# ST_LINK_V2-1.net
KiCad netlist of a schematic drawn in Altium Designer
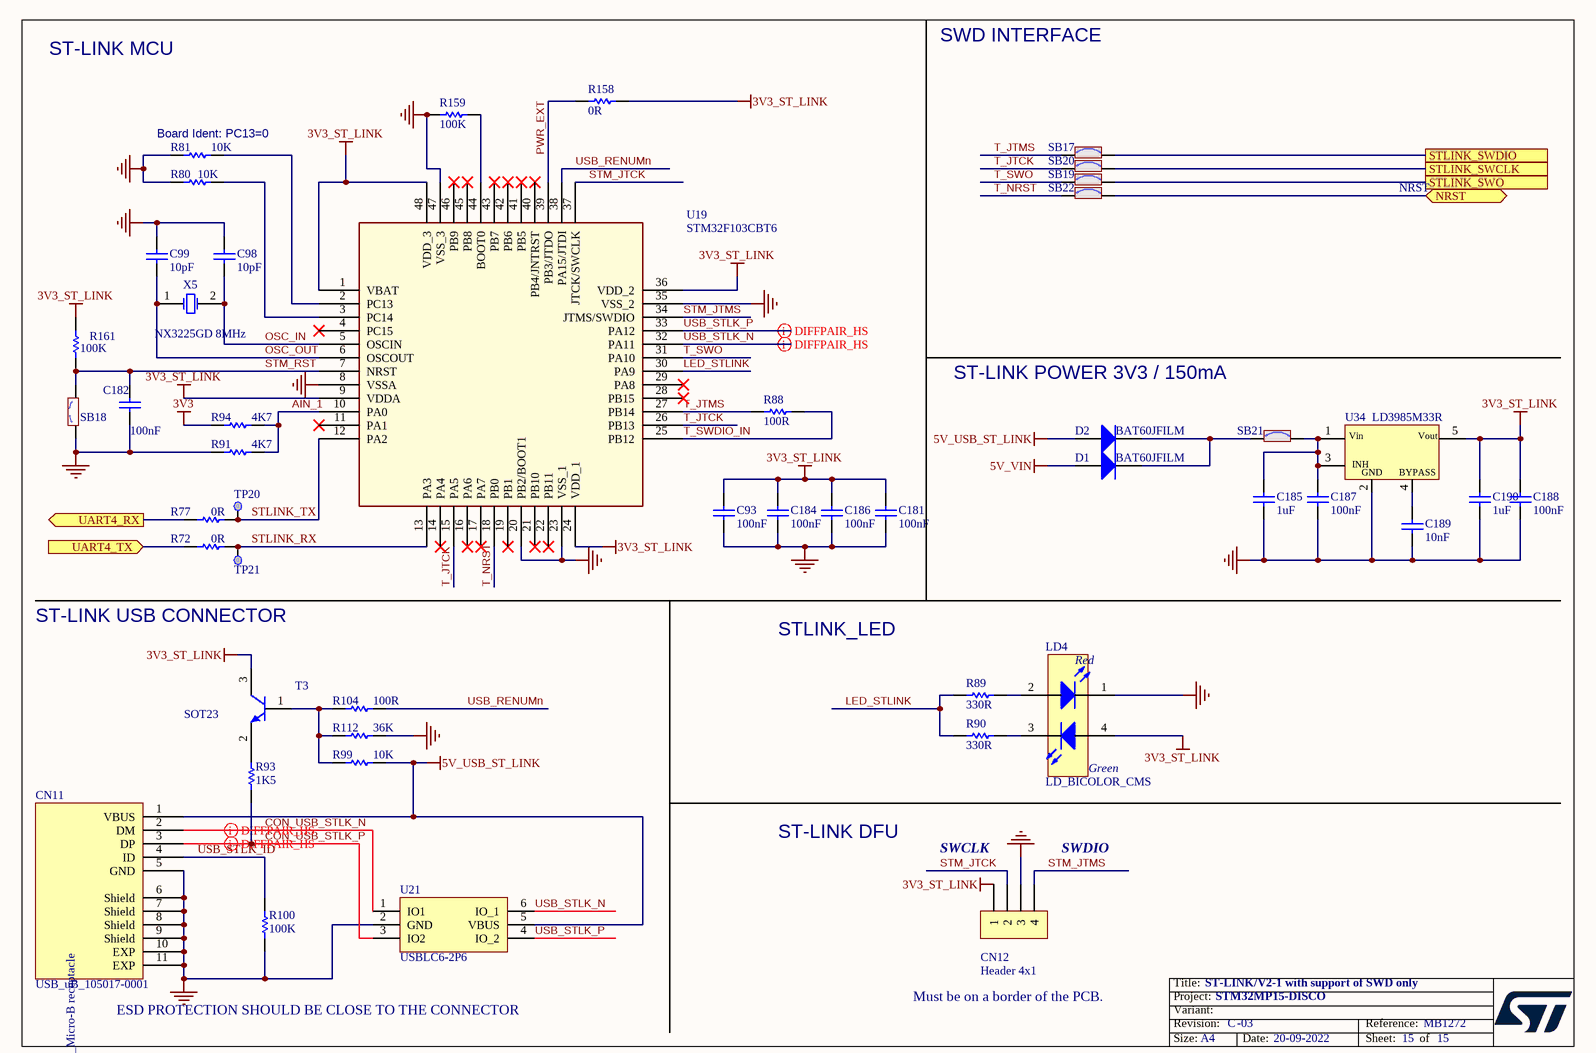
[diagram p0: ST_LINK_V2-1.SCHDOC]

(export (version "E")
  (design (tool "Eeschema 10.0.6"))
  (components
    (comp (ref "C93")
      (value "100nF")
      (footprint "C0402")
      (description "Capacitor,100nF,16V,X7R,10%,0402")
      (fields
        (field (name "INTERNAL_PART_NUMBER") "MCD-00006")
        (field (name "MANUFACTURER_PART_NUMBER") "CC0402KRX7R7BB104")
        (field (name "PROVIDED_BY") "SUBCO")
      )
      (libsource (lib "MCD_PARTS_database") (part "Capacitor"))
    )
    (comp (ref "C98")
      (value "10pF")
      (footprint "C0402")
      (description "Capacitor,10pF,50V,NPO,5%,0402")
      (fields
        (field (name "INTERNAL_PART_NUMBER") "MCD-00015")
        (field (name "MANUFACTURER_PART_NUMBER") "CC0402JRNPO9BN100")
        (field (name "PROVIDED_BY") "SUBCO")
      )
      (libsource (lib "MCD_PARTS_database") (part "Capacitor"))
    )
    (comp (ref "C99")
      (value "10pF")
      (footprint "C0402")
      (description "Capacitor,10pF,50V,NPO,5%,0402")
      (fields
        (field (name "INTERNAL_PART_NUMBER") "MCD-00015")
        (field (name "MANUFACTURER_PART_NUMBER") "CC0402JRNPO9BN100")
        (field (name "PROVIDED_BY") "SUBCO")
      )
      (libsource (lib "MCD_PARTS_database") (part "Capacitor"))
    )
    (comp (ref "C181")
      (value "100nF")
      (footprint "C0402")
      (description "Capacitor,100nF,16V,X7R,10%,0402")
      (fields
        (field (name "INTERNAL_PART_NUMBER") "MCD-00006")
        (field (name "MANUFACTURER_PART_NUMBER") "CC0402KRX7R7BB104")
        (field (name "PROVIDED_BY") "SUBCO")
      )
      (libsource (lib "MCD_PARTS_database") (part "Capacitor"))
    )
    (comp (ref "C182")
      (value "100nF")
      (footprint "C0402")
      (description "Capacitor,100nF,16V,X7R,10%,0402")
      (fields
        (field (name "INTERNAL_PART_NUMBER") "MCD-00006")
        (field (name "MANUFACTURER_PART_NUMBER") "CC0402KRX7R7BB104")
        (field (name "PROVIDED_BY") "SUBCO")
      )
      (libsource (lib "MCD_PARTS_database") (part "Capacitor"))
    )
    (comp (ref "C184")
      (value "100nF")
      (footprint "C0402")
      (description "Capacitor,100nF,16V,X7R,10%,0402")
      (fields
        (field (name "INTERNAL_PART_NUMBER") "MCD-00006")
        (field (name "MANUFACTURER_PART_NUMBER") "CC0402KRX7R7BB104")
        (field (name "PROVIDED_BY") "SUBCO")
      )
      (libsource (lib "MCD_PARTS_database") (part "Capacitor"))
    )
    (comp (ref "C185")
      (value "1uF")
      (footprint "C0603")
      (description "Capacitor,1uF,6V3,X5R,10%,0603")
      (fields
        (field (name "INTERNAL_PART_NUMBER") "MCD-00238")
        (field (name "MANUFACTURER_PART_NUMBER") "CC0603KRX5R5BB105")
        (field (name "PROVIDED_BY") "SUBCO")
      )
      (libsource (lib "MCD_PARTS_database") (part "Capacitor"))
    )
    (comp (ref "C186")
      (value "100nF")
      (footprint "C0402")
      (description "Capacitor,100nF,16V,X7R,10%,0402")
      (fields
        (field (name "INTERNAL_PART_NUMBER") "MCD-00006")
        (field (name "MANUFACTURER_PART_NUMBER") "CC0402KRX7R7BB104")
        (field (name "PROVIDED_BY") "SUBCO")
      )
      (libsource (lib "MCD_PARTS_database") (part "Capacitor"))
    )
    (comp (ref "C187")
      (value "100nF")
      (footprint "C0402")
      (description "Capacitor,100nF,16V,X7R,10%,0402")
      (fields
        (field (name "INTERNAL_PART_NUMBER") "MCD-00006")
        (field (name "MANUFACTURER_PART_NUMBER") "CC0402KRX7R7BB104")
        (field (name "PROVIDED_BY") "SUBCO")
      )
      (libsource (lib "MCD_PARTS_database") (part "Capacitor"))
    )
    (comp (ref "C188")
      (value "100nF")
      (footprint "C0402")
      (description "Capacitor,100nF,16V,X7R,10%,0402")
      (fields
        (field (name "INTERNAL_PART_NUMBER") "MCD-00006")
        (field (name "MANUFACTURER_PART_NUMBER") "CC0402KRX7R7BB104")
        (field (name "PROVIDED_BY") "SUBCO")
      )
      (libsource (lib "MCD_PARTS_database") (part "Capacitor"))
    )
    (comp (ref "C189")
      (value "10nF")
      (footprint "C0402")
      (description "Capacitor,10nF,16V,X7R,10%,0402")
      (fields
        (field (name "INTERNAL_PART_NUMBER") "MCD-00011")
        (field (name "MANUFACTURER_PART_NUMBER") "CC0402KRX7R7BB103")
        (field (name "PROVIDED_BY") "SUBCO")
      )
      (libsource (lib "MCD_PARTS_database") (part "Capacitor"))
    )
    (comp (ref "C190")
      (value "1uF")
      (footprint "C0603")
      (description "Capacitor,1uF,6V3,X5R,10%,0603")
      (fields
        (field (name "INTERNAL_PART_NUMBER") "MCD-00238")
        (field (name "MANUFACTURER_PART_NUMBER") "CC0603KRX5R5BB105")
        (field (name "PROVIDED_BY") "SUBCO")
      )
      (libsource (lib "MCD_PARTS_database") (part "Capacitor"))
    )
    (comp (ref "CN11")
      (value "USB_uB_105017-0001")
      (footprint "CON_USBMICROB_MOLEX_105017-0001_H2P90")
      (description "USB-MICRO-B, 0.65mm, RA, SMT, Bottom Mount,")
      (fields
        (field (name "INTERNAL_PART_NUMBER") "MCD-00028")
        (field (name "MANUFACTURER_PART_NUMBER") "1050170001")
        (field (name "PROVIDED_BY") "SUBCO")
      )
      (libsource (lib "MCD_PARTS_database") (part "USB_uB_105017.0001"))
    )
    (comp (ref "CN12")
      (value "Header 4x1")
      (footprint "CON_SAMTEC_TSW-104-07-G-S")
      (description "Header, 4x1, 2,54mm, VR, TH, Height 5.84mm/2.54mm")
      (fields
        (field (name "INTERNAL_PART_NUMBER") "MCD-00029")
        (field (name "MANUFACTURER_PART_NUMBER") "TSW-104-07-x-S")
        (field (name "PROVIDED_BY") "SUBCO")
      )
      (libsource (lib "MCD_PARTS_database") (part "Header 4x1"))
    )
    (comp (ref "D1")
      (value "BAT60JFILM")
      (footprint "DIO_SOD323")
      (fields
        (field (name "INTERNAL_PART_NUMBER") "MCD-00034")
        (field (name "MANUFACTURER") "STMICROELECTRONICS")
        (field (name "BMS_PART_NUMBER") "9151097")
        (field (name "PROVIDED_BY") "SUBCO with ST control")
      )
      (libsource (lib "MCD_PARTS_database") (part "BAT60JFILM"))
    )
    (comp (ref "D2")
      (value "BAT60JFILM")
      (footprint "DIO_SOD323")
      (fields
        (field (name "INTERNAL_PART_NUMBER") "MCD-00034")
        (field (name "MANUFACTURER") "STMICROELECTRONICS")
        (field (name "BMS_PART_NUMBER") "9151097")
        (field (name "PROVIDED_BY") "SUBCO with ST control")
      )
      (libsource (lib "MCD_PARTS_database") (part "BAT60JFILM"))
    )
    (comp (ref "LD4")
      (value "LD_BICOLOR_CMS")
      (footprint "LED_BI-GR_HSMF-A201-A00J1")
      (description "LED Bicolor")
      (fields (field (name "INTERNAL_PART_NUMBER") "MCD-02402") (field (name "MANUFACTURER") "EVERLIGHT"))
      (libsource (lib "MCD_PARTS_database") (part "LD_BICOLOR_CMS"))
    )
    (comp (ref "R72")
      (value "0R")
      (footprint "R0402")
      (description "Resistor,0R,0402,5%,1/16W")
      (fields
        (field (name "INTERNAL_PART_NUMBER") "MCD-00052")
        (field (name "MANUFACTURER_PART_NUMBER") "RC0402JR-070RL")
        (field (name "PROVIDED_BY") "SUBCO")
      )
      (libsource (lib "MCD_PARTS_database") (part "Resistor"))
    )
    (comp (ref "R77")
      (value "0R")
      (footprint "R0402")
      (description "Resistor,0R,0402,5%,1/16W")
      (fields
        (field (name "INTERNAL_PART_NUMBER") "MCD-00052")
        (field (name "MANUFACTURER_PART_NUMBER") "RC0402JR-070RL")
        (field (name "PROVIDED_BY") "SUBCO")
      )
      (libsource (lib "MCD_PARTS_database") (part "Resistor"))
    )
    (comp (ref "R80")
      (value "10K")
      (footprint "R0402")
      (description "Resistor,10K,0402,1%,1/16W")
      (fields
        (field (name "INTERNAL_PART_NUMBER") "MCD-00053")
        (field (name "MANUFACTURER_PART_NUMBER") "RC0402FR-0710KL")
        (field (name "PROVIDED_BY") "SUBCO")
      )
      (libsource (lib "MCD_PARTS_database") (part "Resistor"))
    )
    (comp (ref "R81")
      (value "10K")
      (footprint "R0402")
      (description "Resistor,10K,0402,1%,1/16W")
      (fields
        (field (name "INTERNAL_PART_NUMBER") "MCD-00053")
        (field (name "MANUFACTURER_PART_NUMBER") "RC0402FR-0710KL")
        (field (name "PROVIDED_BY") "SUBCO")
      )
      (libsource (lib "MCD_PARTS_database") (part "Resistor"))
    )
    (comp (ref "R88")
      (value "100R")
      (footprint "R0402")
      (description "Resistor,100R,0402,1%,1/16W")
      (fields
        (field (name "INTERNAL_PART_NUMBER") "MCD-00067")
        (field (name "MANUFACTURER_PART_NUMBER") "RC0402FR-07100RL")
        (field (name "PROVIDED_BY") "SUBCO")
      )
      (libsource (lib "MCD_PARTS_database") (part "Resistor"))
    )
    (comp (ref "R89")
      (value "330R")
      (footprint "R0402")
      (description "Resistor,330R,0402,1%,1/16W")
      (fields
        (field (name "INTERNAL_PART_NUMBER") "MCD-00062")
        (field (name "MANUFACTURER_PART_NUMBER") "RC0402FR-07330RL")
        (field (name "PROVIDED_BY") "SUBCO")
      )
      (libsource (lib "MCD_PARTS_database") (part "Resistor"))
    )
    (comp (ref "R90")
      (value "330R")
      (footprint "R0402")
      (description "Resistor,330R,0402,1%,1/16W")
      (fields
        (field (name "INTERNAL_PART_NUMBER") "MCD-00062")
        (field (name "MANUFACTURER_PART_NUMBER") "RC0402FR-07330RL")
        (field (name "PROVIDED_BY") "SUBCO")
      )
      (libsource (lib "MCD_PARTS_database") (part "Resistor"))
    )
    (comp (ref "R91")
      (value "4K7")
      (footprint "R0402")
      (description "Resistor,4K7,0402,1%,1/16W")
      (fields
        (field (name "INTERNAL_PART_NUMBER") "MCD-00065")
        (field (name "MANUFACTURER_PART_NUMBER") "RC0402FR-074K7L")
        (field (name "PROVIDED_BY") "SUBCO")
      )
      (libsource (lib "MCD_PARTS_database") (part "Resistor"))
    )
    (comp (ref "R93")
      (value "1K5")
      (footprint "R0402")
      (description "Resistor,1K5,0402,1%,1/16W")
      (fields
        (field (name "INTERNAL_PART_NUMBER") "MCD-00068")
        (field (name "MANUFACTURER_PART_NUMBER") "RC0402FR-071K5L")
        (field (name "PROVIDED_BY") "SUBCO")
      )
      (libsource (lib "MCD_PARTS_database") (part "Resistor"))
    )
    (comp (ref "R94")
      (value "4K7")
      (footprint "R0402")
      (description "Resistor,4K7,0402,1%,1/16W")
      (fields
        (field (name "INTERNAL_PART_NUMBER") "MCD-00065")
        (field (name "MANUFACTURER_PART_NUMBER") "RC0402FR-074K7L")
        (field (name "PROVIDED_BY") "SUBCO")
      )
      (libsource (lib "MCD_PARTS_database") (part "Resistor"))
    )
    (comp (ref "R99")
      (value "10K")
      (footprint "R0402")
      (description "Resistor,10K,0402,1%,1/16W")
      (fields
        (field (name "INTERNAL_PART_NUMBER") "MCD-00053")
        (field (name "MANUFACTURER_PART_NUMBER") "RC0402FR-0710KL")
        (field (name "PROVIDED_BY") "SUBCO")
      )
      (libsource (lib "MCD_PARTS_database") (part "Resistor"))
    )
    (comp (ref "R100")
      (value "100K")
      (footprint "R0402")
      (description "Resistor,100K,0402,1%,1/16W")
      (fields
        (field (name "INTERNAL_PART_NUMBER") "MCD-00059")
        (field (name "MANUFACTURER_PART_NUMBER") "RC0402FR-07100KL")
        (field (name "PROVIDED_BY") "SUBCO")
      )
      (libsource (lib "MCD_PARTS_database") (part "Resistor"))
    )
    (comp (ref "R104")
      (value "100R")
      (footprint "R0402")
      (description "Resistor,100R,0402,1%,1/16W")
      (fields
        (field (name "INTERNAL_PART_NUMBER") "MCD-00067")
        (field (name "MANUFACTURER_PART_NUMBER") "RC0402FR-07100RL")
        (field (name "PROVIDED_BY") "SUBCO")
      )
      (libsource (lib "MCD_PARTS_database") (part "Resistor"))
    )
    (comp (ref "R112")
      (value "36K")
      (footprint "R0402")
      (description "Resistor,36K,0402,1%,1/16W")
      (fields
        (field (name "INTERNAL_PART_NUMBER") "MCD-00069")
        (field (name "MANUFACTURER_PART_NUMBER") "RC0402FR-0736KL")
        (field (name "PROVIDED_BY") "SUBCO")
      )
      (libsource (lib "MCD_PARTS_database") (part "Resistor"))
    )
    (comp (ref "R158")
      (value "0R")
      (footprint "R0402")
      (description "Resistor,0R,0402,5%,1/16W")
      (fields
        (field (name "INTERNAL_PART_NUMBER") "MCD-00052")
        (field (name "MANUFACTURER_PART_NUMBER") "RC0402JR-070RL")
        (field (name "PROVIDED_BY") "SUBCO")
      )
      (libsource (lib "MCD_PARTS_database") (part "Resistor"))
    )
    (comp (ref "R159")
      (value "100K")
      (footprint "R0402")
      (description "Resistor,100K,0402,1%,1/16W")
      (fields
        (field (name "INTERNAL_PART_NUMBER") "MCD-00059")
        (field (name "MANUFACTURER_PART_NUMBER") "RC0402FR-07100KL")
        (field (name "PROVIDED_BY") "SUBCO")
      )
      (libsource (lib "MCD_PARTS_database") (part "Resistor"))
    )
    (comp (ref "R161")
      (value "100K")
      (footprint "R0402")
      (description "Resistor,100K,0402,1%,1/16W")
      (fields
        (field (name "INTERNAL_PART_NUMBER") "MCD-00059")
        (field (name "MANUFACTURER_PART_NUMBER") "RC0402FR-07100KL")
        (field (name "PROVIDED_BY") "SUBCO")
      )
      (libsource (lib "MCD_PARTS_database") (part "Resistor"))
    )
    (comp (ref "SB17")
      (value "~")
      (footprint "SOLDER-BRIDGE_R0603-0R")
      (description "Solder Bridge ON")
      (fields
        (field (name "INTERNAL_PART_NUMBER") "MCD-00071")
        (field (name "MANUFACTURER") "YAGEO")
        (field (name "PROVIDED_BY") "SUBCO")
      )
      (libsource (lib "MCD_PARTS_database") (part "SB_ON"))
    )
    (comp (ref "SB18")
      (value "~")
      (footprint "SOLDER-BRIDGE_R0603-0R")
      (description "Solder Bridge OFF")
      (fields
        (field (name "INTERNAL_PART_NUMBER") "MCD-00072")
        (field (name "MANUFACTURER") "YAGEO")
        (field (name "PROVIDED_BY") "SUBCO")
      )
      (libsource (lib "MCD_PARTS_database") (part "SB_OFF"))
    )
    (comp (ref "SB19")
      (value "~")
      (footprint "SOLDER-BRIDGE_R0603-0R")
      (description "Solder Bridge ON")
      (fields
        (field (name "INTERNAL_PART_NUMBER") "MCD-00071")
        (field (name "MANUFACTURER") "YAGEO")
        (field (name "PROVIDED_BY") "SUBCO")
      )
      (libsource (lib "MCD_PARTS_database") (part "SB_ON"))
    )
    (comp (ref "SB20")
      (value "~")
      (footprint "SOLDER-BRIDGE_R0603-0R")
      (description "Solder Bridge ON")
      (fields
        (field (name "INTERNAL_PART_NUMBER") "MCD-00071")
        (field (name "MANUFACTURER") "YAGEO")
        (field (name "PROVIDED_BY") "SUBCO")
      )
      (libsource (lib "MCD_PARTS_database") (part "SB_ON"))
    )
    (comp (ref "SB21")
      (value "~")
      (footprint "SOLDER-BRIDGE_R0603-0R")
      (description "Solder Bridge ON")
      (fields
        (field (name "INTERNAL_PART_NUMBER") "MCD-00071")
        (field (name "MANUFACTURER") "YAGEO")
        (field (name "PROVIDED_BY") "SUBCO")
      )
      (libsource (lib "MCD_PARTS_database") (part "SB_ON"))
    )
    (comp (ref "SB22")
      (value "~")
      (footprint "SOLDER-BRIDGE_R0603-0R")
      (description "Solder Bridge ON")
      (fields
        (field (name "INTERNAL_PART_NUMBER") "MCD-00071")
        (field (name "MANUFACTURER") "YAGEO")
        (field (name "PROVIDED_BY") "SUBCO")
      )
      (libsource (lib "MCD_PARTS_database") (part "SB_ON"))
    )
    (comp (ref "T3")
      (value "SOT23")
      (footprint "NPN_SOT23")
      (description "NPN Bipolar Transistor")
      (fields
        (field (name "INTERNAL_PART_NUMBER") "MCD-00073")
        (field (name "MANUFACTURER_PART_NUMBER") "BSR14")
        (field (name "PROVIDED_BY") "SUBCO")
      )
      (libsource (lib "MCD_PARTS_database") (part "9013-SOT23"))
    )
    (comp (ref "TP20")
      (value "Test Point")
      (footprint "TP_SMD_1MM")
      (description "Test Point 1mm")
      (fields
        (field (name "INTERNAL_PART_NUMBER") "MCD-00074")
        (field (name "MANUFACTURER_PART_NUMBER") "n/a")
      )
      (libsource (lib "MCD_PARTS_database") (part "Test Point"))
    )
    (comp (ref "TP21")
      (value "Test Point")
      (footprint "TP_SMD_1MM")
      (description "Test Point 1mm")
      (fields
        (field (name "INTERNAL_PART_NUMBER") "MCD-00074")
        (field (name "MANUFACTURER_PART_NUMBER") "n/a")
      )
      (libsource (lib "") (part "Test Point_1"))
    )
    (comp (ref "U19")
      (value "STM32F103CBT6")
      (footprint "ICC_LQFP48_7X7_P050")
      (description "Medium-density performance line ARM-based 32-bit MCU with 128KB Flash")
      (fields
        (field (name "INTERNAL_PART_NUMBER") "MCD-00085")
        (field (name "MANUFACTURER") "STMICROELECTRONICS")
        (field (name "PROVIDED_BY") "SUBCO with ST control")
      )
      (libsource (lib "MCD_PARTS_database") (part "STM32F103CBT6"))
    )
    (comp (ref "U21")
      (value "USBLC6-2P6")
      (footprint "ESD_SOT666")
      (description "USB OTG FS ESD protection")
      (fields
        (field (name "INTERNAL_PART_NUMBER") "MCD-00169")
        (field (name "MANUFACTURER") "STMICROELECTRONICS")
        (field (name "PROVIDED_BY") "SUBCO with ST control")
      )
      (libsource (lib "MCD_PARTS_database") (part "USBLC6-2P6"))
    )
    (comp (ref "U34")
      (value "LD3985M33R")
      (footprint "REG_SOT23-5L")
      (description "Ultra low drop-low noise BiCMOS voltage, regulators low ESR capacitors compatible")
      (fields
        (field (name "INTERNAL_PART_NUMBER") "MCD-00086")
        (field (name "MANUFACTURER") "STMICROELECTRONICS")
        (field (name "PROVIDED_BY") "SUBCO with ST control")
      )
      (libsource (lib "MCD_PARTS_database") (part "LD3985M33R"))
    )
    (comp (ref "X5")
      (value "NX3225GD 8MHz")
      (footprint "CRY_NX3225GD_2P")
      (description "Crystal 8Mhz, 8pF, -+50PPM, SMD")
      (fields
        (field (name "INTERNAL_PART_NUMBER") "MCD-00092")
        (field (name "MANUFACTURER_PART_NUMBER") "NX3225GD 8MHz EXS00A-CG04874")
        (field (name "PROVIDED_BY") "SUBCO")
      )
      (libsource (lib "MCD_PARTS_database") (part "XTAL_8M_NX3225GD"))
    )
  )
  (nets
    (net (code "1") (name "/AIN_1") (class "Default")
      (node (ref "R91") (pin "2") (pinfunction "2_2") (pintype "passive"))
      (node (ref "R94") (pin "2") (pinfunction "2_2") (pintype "passive"))
      (node (ref "U19") (pin "10") (pinfunction "PA0_10") (pintype "passive"))
    )
    (net (code "2") (name "/CON_USB_STLK_N") (class "Default")
      (node (ref "CN11") (pin "2") (pinfunction "DM_2") (pintype "passive"))
      (node (ref "U21") (pin "1") (pinfunction "IO1_1") (pintype "passive"))
    )
    (net (code "3") (name "/CON_USB_STLK_P") (class "Default")
      (node (ref "CN11") (pin "3") (pinfunction "DP_3") (pintype "passive"))
      (node (ref "R93") (pin "1") (pinfunction "1_1") (pintype "passive"))
      (node (ref "U21") (pin "3") (pinfunction "IO2_3") (pintype "passive"))
    )
    (net (code "4") (name "/LED_STLINK") (class "Default")
      (node (ref "R89") (pin "2") (pinfunction "2_2") (pintype "passive"))
      (node (ref "R90") (pin "2") (pinfunction "2_2") (pintype "passive"))
      (node (ref "U19") (pin "30") (pinfunction "PA9_30") (pintype "passive"))
    )
    (net (code "5") (name "/NRST") (class "Default")
      (node (ref "SB22") (pin "2") (pinfunction "2_2") (pintype "passive"))
    )
    (net (code "6") (name "/OSC_IN") (class "Default")
      (node (ref "C98") (pin "1") (pinfunction "1_1") (pintype "passive"))
      (node (ref "U19") (pin "5") (pinfunction "OSCIN_5") (pintype "passive"))
      (node (ref "X5") (pin "2") (pinfunction "OSC2_2") (pintype "passive"))
    )
    (net (code "7") (name "/OSC_OUT") (class "Default")
      (node (ref "C99") (pin "1") (pinfunction "1_1") (pintype "passive"))
      (node (ref "U19") (pin "6") (pinfunction "OSCOUT_6") (pintype "passive"))
      (node (ref "X5") (pin "1") (pinfunction "OSC1_1") (pintype "passive"))
    )
    (net (code "8") (name "/PWR_EXT") (class "Default")
      (node (ref "R158") (pin "1") (pinfunction "1_1") (pintype "passive"))
      (node (ref "U19") (pin "39") (pinfunction "PB3/JTDO_39") (pintype "passive"))
    )
    (net (code "9") (name "/STLINK_RX") (class "Default")
      (node (ref "R72") (pin "2") (pinfunction "2_2") (pintype "passive"))
      (node (ref "TP21") (pin "1") (pinfunction "1_1") (pintype "passive"))
      (node (ref "U19") (pin "13") (pinfunction "PA3_13") (pintype "passive"))
    )
    (net (code "10") (name "/STLINK_SWCLK") (class "Default")
      (node (ref "SB20") (pin "2") (pinfunction "2_2") (pintype "passive"))
    )
    (net (code "11") (name "/STLINK_SWDIO") (class "Default")
      (node (ref "SB17") (pin "2") (pinfunction "2_2") (pintype "passive"))
    )
    (net (code "12") (name "/STLINK_SWO") (class "Default")
      (node (ref "SB19") (pin "2") (pinfunction "2_2") (pintype "passive"))
    )
    (net (code "13") (name "/STLINK_TX") (class "Default")
      (node (ref "R77") (pin "1") (pinfunction "1_1") (pintype "passive"))
      (node (ref "TP20") (pin "1") (pinfunction "1_1") (pintype "passive"))
      (node (ref "U19") (pin "12") (pinfunction "PA2_12") (pintype "passive"))
    )
    (net (code "14") (name "/STM_JTCK") (class "Default")
      (node (ref "CN12") (pin "2") (pinfunction "2_2") (pintype "passive"))
      (node (ref "U19") (pin "37") (pinfunction "JTCK/SWCLK_37") (pintype "passive"))
    )
    (net (code "15") (name "/STM_JTMS") (class "Default")
      (node (ref "CN12") (pin "4") (pinfunction "4_4") (pintype "passive"))
      (node (ref "U19") (pin "34") (pinfunction "JTMS/SWDIO_34") (pintype "passive"))
    )
    (net (code "16") (name "/STM_RST") (class "Default")
      (node (ref "C182") (pin "2") (pinfunction "2_2") (pintype "passive"))
      (node (ref "R161") (pin "1") (pinfunction "1_1") (pintype "passive"))
      (node (ref "SB18") (pin "2") (pinfunction "2_2") (pintype "passive"))
      (node (ref "U19") (pin "7") (pinfunction "NRST_7") (pintype "passive"))
    )
    (net (code "17") (name "/T_JTCK") (class "Default")
      (node (ref "SB20") (pin "1") (pinfunction "1_1") (pintype "passive"))
      (node (ref "U19") (pin "15") (pinfunction "PA5_15") (pintype "passive"))
      (node (ref "U19") (pin "26") (pinfunction "PB13_26") (pintype "passive"))
    )
    (net (code "18") (name "/T_JTMS") (class "Default")
      (node (ref "R88") (pin "1") (pinfunction "1_1") (pintype "passive"))
      (node (ref "SB17") (pin "1") (pinfunction "1_1") (pintype "passive"))
      (node (ref "U19") (pin "27") (pinfunction "PB14_27") (pintype "passive"))
    )
    (net (code "19") (name "/T_NRST") (class "Default")
      (node (ref "SB22") (pin "1") (pinfunction "1_1") (pintype "passive"))
      (node (ref "U19") (pin "18") (pinfunction "PB0_18") (pintype "passive"))
    )
    (net (code "20") (name "/T_SWDIO_IN") (class "Default")
      (node (ref "R88") (pin "2") (pinfunction "2_2") (pintype "passive"))
      (node (ref "U19") (pin "25") (pinfunction "PB12_25") (pintype "passive"))
    )
    (net (code "21") (name "/T_SWO") (class "Default")
      (node (ref "SB19") (pin "1") (pinfunction "1_1") (pintype "passive"))
      (node (ref "U19") (pin "31") (pinfunction "PA10_31") (pintype "passive"))
    )
    (net (code "22") (name "/UART4_RX") (class "Default")
      (node (ref "R77") (pin "2") (pinfunction "2_2") (pintype "passive"))
    )
    (net (code "23") (name "/UART4_TX") (class "Default")
      (node (ref "R72") (pin "1") (pinfunction "1_1") (pintype "passive"))
    )
    (net (code "24") (name "/USB_RENUMn") (class "Default")
      (node (ref "R104") (pin "2") (pinfunction "2_2") (pintype "passive"))
      (node (ref "U19") (pin "38") (pinfunction "PA15/JTDI_38") (pintype "passive"))
    )
    (net (code "25") (name "/USB_STLK_ID") (class "Default")
      (node (ref "CN11") (pin "4") (pinfunction "ID_4") (pintype "passive"))
      (node (ref "R100") (pin "2") (pinfunction "2_2") (pintype "passive"))
    )
    (net (code "26") (name "/USB_STLK_N") (class "Default")
      (node (ref "U19") (pin "32") (pinfunction "PA11_32") (pintype "passive"))
      (node (ref "U21") (pin "6") (pinfunction "IO_1_6") (pintype "passive"))
    )
    (net (code "27") (name "/USB_STLK_P") (class "Default")
      (node (ref "U19") (pin "33") (pinfunction "PA12_33") (pintype "passive"))
      (node (ref "U21") (pin "4") (pinfunction "IO_2_4") (pintype "passive"))
    )
    (net (code "28") (name "3V3") (class "Default")
      (node (ref "R94") (pin "1") (pinfunction "1_1") (pintype "passive"))
    )
    (net (code "29") (name "3V3_ST_LINK") (class "Default")
      (node (ref "C181") (pin "2") (pinfunction "2_2") (pintype "passive"))
      (node (ref "C184") (pin "2") (pinfunction "2_2") (pintype "passive"))
      (node (ref "C186") (pin "2") (pinfunction "2_2") (pintype "passive"))
      (node (ref "C188") (pin "2") (pinfunction "2_2") (pintype "passive"))
      (node (ref "C190") (pin "2") (pinfunction "2_2") (pintype "passive"))
      (node (ref "C93") (pin "2") (pinfunction "2_2") (pintype "passive"))
      (node (ref "CN12") (pin "1") (pinfunction "1_1") (pintype "passive"))
      (node (ref "LD4") (pin "4") (pinfunction "YellowGreen_anode_4") (pintype "passive"))
      (node (ref "R158") (pin "2") (pinfunction "2_2") (pintype "passive"))
      (node (ref "R161") (pin "2") (pinfunction "2_2") (pintype "passive"))
      (node (ref "T3") (pin "3") (pinfunction "C_3") (pintype "passive"))
      (node (ref "U19") (pin "1") (pinfunction "VBAT_1") (pintype "passive"))
      (node (ref "U19") (pin "24") (pinfunction "VDD_1_24") (pintype "passive"))
      (node (ref "U19") (pin "36") (pinfunction "VDD_2_36") (pintype "passive"))
      (node (ref "U19") (pin "48") (pinfunction "VDD_3_48") (pintype "passive"))
      (node (ref "U19") (pin "9") (pinfunction "VDDA_9") (pintype "passive"))
      (node (ref "U34") (pin "5") (pinfunction "Vout_5") (pintype "passive"))
    )
    (net (code "30") (name "5V_USB_ST_LINK") (class "Default")
      (node (ref "CN11") (pin "1") (pinfunction "VBUS_1") (pintype "passive"))
      (node (ref "D2") (pin "1") (pinfunction "A_1") (pintype "passive"))
      (node (ref "R99") (pin "1") (pinfunction "1_1") (pintype "passive"))
      (node (ref "U21") (pin "5") (pinfunction "VBUS_5") (pintype "passive"))
    )
    (net (code "31") (name "5V_VIN") (class "Default")
      (node (ref "D1") (pin "1") (pinfunction "A_1") (pintype "passive"))
    )
    (net (code "32") (name "GND") (class "Default")
      (node (ref "C181") (pin "1") (pinfunction "1_1") (pintype "passive"))
      (node (ref "C182") (pin "1") (pinfunction "1_1") (pintype "passive"))
      (node (ref "C184") (pin "1") (pinfunction "1_1") (pintype "passive"))
      (node (ref "C185") (pin "2") (pinfunction "2_2") (pintype "passive"))
      (node (ref "C186") (pin "1") (pinfunction "1_1") (pintype "passive"))
      (node (ref "C187") (pin "1") (pinfunction "1_1") (pintype "passive"))
      (node (ref "C188") (pin "1") (pinfunction "1_1") (pintype "passive"))
      (node (ref "C189") (pin "1") (pinfunction "1_1") (pintype "passive"))
      (node (ref "C190") (pin "1") (pinfunction "1_1") (pintype "passive"))
      (node (ref "C93") (pin "1") (pinfunction "1_1") (pintype "passive"))
      (node (ref "C98") (pin "2") (pinfunction "2_2") (pintype "passive"))
      (node (ref "C99") (pin "2") (pinfunction "2_2") (pintype "passive"))
      (node (ref "CN11") (pin "10") (pinfunction "EXP_10") (pintype "passive"))
      (node (ref "CN11") (pin "11") (pinfunction "EXP_11") (pintype "passive"))
      (node (ref "CN11") (pin "5") (pinfunction "GND_5") (pintype "passive"))
      (node (ref "CN11") (pin "6") (pinfunction "Shield_6") (pintype "passive"))
      (node (ref "CN11") (pin "7") (pinfunction "Shield_7") (pintype "passive"))
      (node (ref "CN11") (pin "8") (pinfunction "Shield_8") (pintype "passive"))
      (node (ref "CN11") (pin "9") (pinfunction "Shield_9") (pintype "passive"))
      (node (ref "CN12") (pin "3") (pinfunction "3_3") (pintype "passive"))
      (node (ref "LD4") (pin "1") (pinfunction "RED_cathode_1") (pintype "passive"))
      (node (ref "R100") (pin "1") (pinfunction "1_1") (pintype "passive"))
      (node (ref "R112") (pin "1") (pinfunction "1_1") (pintype "passive"))
      (node (ref "R159") (pin "1") (pinfunction "1_1") (pintype "passive"))
      (node (ref "R80") (pin "1") (pinfunction "1_1") (pintype "passive"))
      (node (ref "R81") (pin "2") (pinfunction "2_2") (pintype "passive"))
      (node (ref "R91") (pin "1") (pinfunction "1_1") (pintype "passive"))
      (node (ref "SB18") (pin "1") (pinfunction "1_1") (pintype "passive"))
      (node (ref "U19") (pin "20") (pinfunction "PB2/BOOT1_20") (pintype "passive"))
      (node (ref "U19") (pin "23") (pinfunction "VSS_1_23") (pintype "passive"))
      (node (ref "U19") (pin "35") (pinfunction "VSS_2_35") (pintype "passive"))
      (node (ref "U19") (pin "47") (pinfunction "VSS_3_47") (pintype "passive"))
      (node (ref "U19") (pin "8") (pinfunction "VSSA_8") (pintype "passive"))
      (node (ref "U21") (pin "2") (pinfunction "GND_2") (pintype "passive"))
      (node (ref "U34") (pin "2") (pinfunction "GND_2") (pintype "passive"))
    )
    (net (code "33") (name "Net-(D1-K)") (class "Default")
      (node (ref "D1") (pin "2") (pinfunction "K_2") (pintype "passive"))
      (node (ref "D2") (pin "2") (pinfunction "K_2") (pintype "passive"))
      (node (ref "SB21") (pin "1") (pinfunction "1_1") (pintype "passive"))
    )
    (net (code "34") (name "Net-(LD4-Red_anode)") (class "Default")
      (node (ref "LD4") (pin "2") (pinfunction "Red_anode_2") (pintype "passive"))
      (node (ref "R89") (pin "1") (pinfunction "1_1") (pintype "passive"))
    )
    (net (code "35") (name "Net-(LD4-YellowGreen_cathode)") (class "Default")
      (node (ref "LD4") (pin "3") (pinfunction "YellowGreen_cathode_3") (pintype "passive"))
      (node (ref "R90") (pin "1") (pinfunction "1_1") (pintype "passive"))
    )
    (net (code "36") (name "Net-(T3-B)") (class "Default")
      (node (ref "R104") (pin "1") (pinfunction "1_1") (pintype "passive"))
      (node (ref "R112") (pin "2") (pinfunction "2_2") (pintype "passive"))
      (node (ref "R99") (pin "2") (pinfunction "2_2") (pintype "passive"))
      (node (ref "T3") (pin "1") (pinfunction "B_1") (pintype "passive"))
    )
    (net (code "37") (name "Net-(T3-E)") (class "Default")
      (node (ref "R93") (pin "2") (pinfunction "2_2") (pintype "passive"))
      (node (ref "T3") (pin "2") (pinfunction "E_2") (pintype "passive"))
    )
    (net (code "38") (name "Net-(U19-BOOT0)") (class "Default")
      (node (ref "R159") (pin "2") (pinfunction "2_2") (pintype "passive"))
      (node (ref "U19") (pin "44") (pinfunction "BOOT0_44") (pintype "passive"))
    )
    (net (code "39") (name "Net-(U19-PC13)") (class "Default")
      (node (ref "R81") (pin "1") (pinfunction "1_1") (pintype "passive"))
      (node (ref "U19") (pin "2") (pinfunction "PC13_2") (pintype "passive"))
    )
    (net (code "40") (name "Net-(U19-PC14)") (class "Default")
      (node (ref "R80") (pin "2") (pinfunction "2_2") (pintype "passive"))
      (node (ref "U19") (pin "3") (pinfunction "PC14_3") (pintype "passive"))
    )
    (net (code "41") (name "Net-(U34-BYPASS)") (class "Default")
      (node (ref "C189") (pin "2") (pinfunction "2_2") (pintype "passive"))
      (node (ref "U34") (pin "4") (pinfunction "BYPASS_4") (pintype "passive"))
    )
    (net (code "42") (name "Net-(U34-CE)") (class "Default")
      (node (ref "C185") (pin "1") (pinfunction "1_1") (pintype "passive"))
      (node (ref "C187") (pin "2") (pinfunction "2_2") (pintype "passive"))
      (node (ref "SB21") (pin "2") (pinfunction "2_2") (pintype "passive"))
      (node (ref "U34") (pin "1") (pinfunction "Vin_1") (pintype "passive"))
      (node (ref "U34") (pin "3") (pinfunction "CE_3") (pintype "passive"))
    )
    (net (code "43") (name "unconnected-(U19-PA1-Pad11)") (class "Default")
      (node (ref "U19") (pin "11") (pinfunction "PA1_11") (pintype "passive+no_connect"))
    )
    (net (code "44") (name "unconnected-(U19-PA4-Pad14)") (class "Default")
      (node (ref "U19") (pin "14") (pinfunction "PA4_14") (pintype "passive+no_connect"))
    )
    (net (code "45") (name "unconnected-(U19-PA6-Pad16)") (class "Default")
      (node (ref "U19") (pin "16") (pinfunction "PA6_16") (pintype "passive+no_connect"))
    )
    (net (code "46") (name "unconnected-(U19-PA7-Pad17)") (class "Default")
      (node (ref "U19") (pin "17") (pinfunction "PA7_17") (pintype "passive+no_connect"))
    )
    (net (code "47") (name "unconnected-(U19-PA8-Pad29)") (class "Default")
      (node (ref "U19") (pin "29") (pinfunction "PA8_29") (pintype "passive+no_connect"))
    )
    (net (code "48") (name "unconnected-(U19-PB1-Pad19)") (class "Default")
      (node (ref "U19") (pin "19") (pinfunction "PB1_19") (pintype "passive+no_connect"))
    )
    (net (code "49") (name "unconnected-(U19-PB4{slash}JNTRST-Pad40)") (class "Default")
      (node (ref "U19") (pin "40") (pinfunction "PB4/JNTRST_40") (pintype "passive+no_connect"))
    )
    (net (code "50") (name "unconnected-(U19-PB5-Pad41)") (class "Default")
      (node (ref "U19") (pin "41") (pinfunction "PB5_41") (pintype "passive+no_connect"))
    )
    (net (code "51") (name "unconnected-(U19-PB6-Pad42)") (class "Default")
      (node (ref "U19") (pin "42") (pinfunction "PB6_42") (pintype "passive+no_connect"))
    )
    (net (code "52") (name "unconnected-(U19-PB7-Pad43)") (class "Default")
      (node (ref "U19") (pin "43") (pinfunction "PB7_43") (pintype "passive+no_connect"))
    )
    (net (code "53") (name "unconnected-(U19-PB8-Pad45)") (class "Default")
      (node (ref "U19") (pin "45") (pinfunction "PB8_45") (pintype "passive+no_connect"))
    )
    (net (code "54") (name "unconnected-(U19-PB9-Pad46)") (class "Default")
      (node (ref "U19") (pin "46") (pinfunction "PB9_46") (pintype "passive+no_connect"))
    )
    (net (code "55") (name "unconnected-(U19-PB10-Pad21)") (class "Default")
      (node (ref "U19") (pin "21") (pinfunction "PB10_21") (pintype "passive+no_connect"))
    )
    (net (code "56") (name "unconnected-(U19-PB11-Pad22)") (class "Default")
      (node (ref "U19") (pin "22") (pinfunction "PB11_22") (pintype "passive+no_connect"))
    )
    (net (code "57") (name "unconnected-(U19-PB15-Pad28)") (class "Default")
      (node (ref "U19") (pin "28") (pinfunction "PB15_28") (pintype "passive+no_connect"))
    )
    (net (code "58") (name "unconnected-(U19-PC15-Pad4)") (class "Default")
      (node (ref "U19") (pin "4") (pinfunction "PC15_4") (pintype "passive+no_connect"))
    )
  )
)
